# 02__Sensors_Sheet.net
KiCad netlist of a schematic drawn in Altium Designer
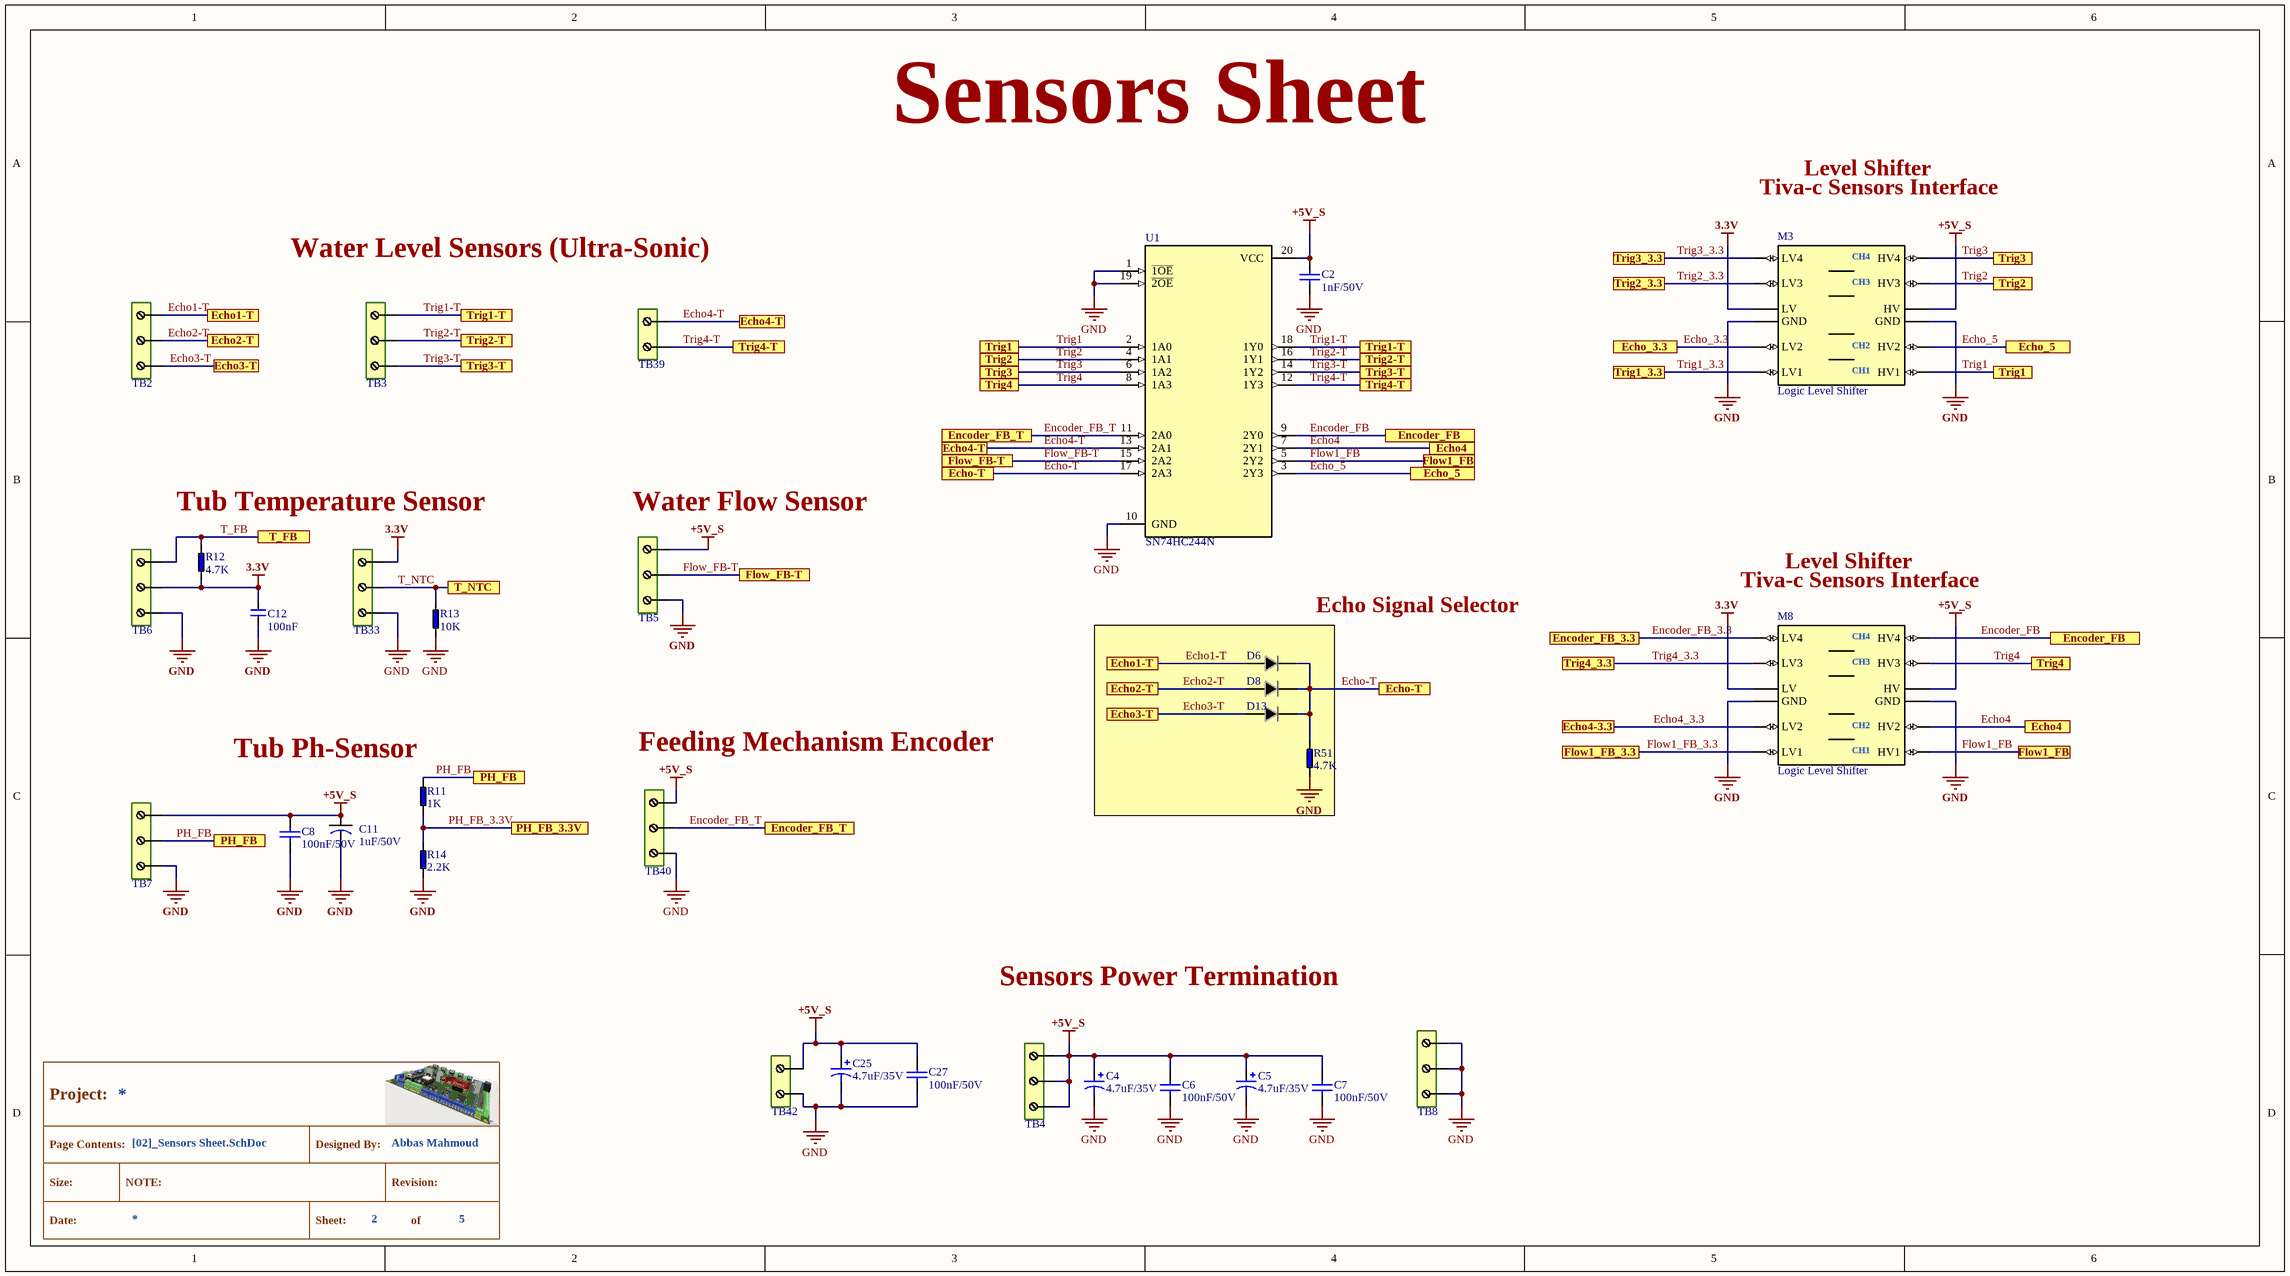
[diagram p0: [02]_Sensors Sheet.SchDoc]

(export (version "E")
  (design (tool "Eeschema 10.0.6"))
  (components
    (comp (ref "*")
      (value "Title Block")
      (description "Moatley Title Block")
      (libsource (lib "Altium_Abbas") (part "Title Block"))
    )
    (comp (ref "C2")
      (value "1nF/50V")
      (footprint "CCAP - PACKAGE - THT ,P = 2.54 MM")
      (description "1nF ±20% 50V Through Hole,P=2.54mm Ceramic Disc Capacitors RoHS")
      (libsource (lib "Altium_Abbas_V3") (part "CCAP - 1nF - 50V - THT - P = 2.54"))
    )
    (comp (ref "C4")
      (value "4.7uF/35V")
      (footprint "ECAP - THT - 5X11X2MM")
      (description "4.7uF ±20% 35V 5x11 7000Hrs @ 105℃ Radial,5x11mm Aluminum Electrolytic Capacitors - Leaded RoHS")
      (libsource (lib "Altium_Abbas_V3") (part "ECAP - 4.7uF - 35V"))
    )
    (comp (ref "C5")
      (value "4.7uF/35V")
      (footprint "ECAP - THT - 5X11X2MM")
      (description "4.7uF ±20% 35V 5x11 7000Hrs @ 105℃ Radial,5x11mm Aluminum Electrolytic Capacitors - Leaded RoHS")
      (libsource (lib "Altium_Abbas_V3") (part "ECAP - 4.7uF - 35V"))
    )
    (comp (ref "C6")
      (value "100nF/50V")
      (footprint "CCAP - PACKAGE - THT ,P = 2.54 MM")
      (description "100nF -20%~+80% 50V Through Hole,P=2.54mm Ceramic Disc Capacitors RoHS")
      (libsource (lib "Altium_Abbas_V3") (part "CCAP - 100nF - 50V - THT - P = 2.54"))
    )
    (comp (ref "C7")
      (value "100nF/50V")
      (footprint "CCAP - PACKAGE - THT ,P = 2.54 MM")
      (description "100nF -20%~+80% 50V Through Hole,P=2.54mm Ceramic Disc Capacitors RoHS")
      (libsource (lib "Altium_Abbas_V3") (part "CCAP - 100nF - 50V - THT - P = 2.54"))
    )
    (comp (ref "C8")
      (value "100nF/50V")
      (footprint "CCAP - PACKAGE - THT ,P = 2.54 MM")
      (description "100nF -20%~+80% 50V Through Hole,P=2.54mm Ceramic Disc Capacitors RoHS")
      (libsource (lib "Altium_Abbas_V3") (part "CCAP - 100nF - 50V - THT - P = 2.54"))
    )
    (comp (ref "C11")
      (value "1uF/50V")
      (footprint "ECAP 5X11X2MM")
      (description "1uF ±20% 50V 5x11 1000Hrs @ 105℃ Radial,5x11mm Aluminum Electrolytic Capacitors - Leaded RoHS")
      (libsource (lib "Altium_Abbas") (part "ECAP-1uF-50V"))
    )
    (comp (ref "C12")
      (value "100nF")
      (footprint "CCAP 0.1 N Y")
      (libsource (lib "Altium_Abbas") (part "Ceramic_CAP_100nF"))
    )
    (comp (ref "C25")
      (value "4.7uF/35V")
      (footprint "ECAP - THT - 5X11X2MM")
      (description "4.7uF ±20% 35V 5x11 7000Hrs @ 105℃ Radial,5x11mm Aluminum Electrolytic Capacitors - Leaded RoHS")
      (libsource (lib "Altium_Abbas_V3") (part "ECAP - 4.7uF - 35V"))
    )
    (comp (ref "C27")
      (value "100nF/50V")
      (footprint "CCAP - PACKAGE - THT ,P = 2.54 MM")
      (description "100nF -20%~+80% 50V Through Hole,P=2.54mm Ceramic Disc Capacitors RoHS")
      (libsource (lib "Altium_Abbas_V3") (part "CCAP - 100nF - 50V - THT - P = 2.54"))
    )
    (comp (ref "D6")
      (value "1N4007")
      (footprint "DIODE - THT - 2.54P - PACKAGE - DO-41")
      (description "1kV 1A 1V @ 1A DO-41 Diodes - General Purpose RoHS")
      (libsource (lib "Altium_Abbas_V3") (part "Diode - 1N4007 - THT"))
    )
    (comp (ref "D8")
      (value "1N4007")
      (footprint "DIODE - THT - 2.54P - PACKAGE - DO-41")
      (description "1kV 1A 1V @ 1A DO-41 Diodes - General Purpose RoHS")
      (libsource (lib "Altium_Abbas_V3") (part "Diode - 1N4007 - THT"))
    )
    (comp (ref "D13")
      (value "1N4007")
      (footprint "DIODE - THT - 2.54P - PACKAGE - DO-41")
      (description "1kV 1A 1V @ 1A DO-41 Diodes - General Purpose RoHS")
      (libsource (lib "Altium_Abbas_V3") (part "Diode - 1N4007 - THT"))
    )
    (comp (ref "M3")
      (value "Logic Level Shifter")
      (footprint "Logic Level Shifter")
      (description "Logic Level Converter Bi-Directional - Works with 5V / 3.3V / 2.8V / 1.8V")
      (libsource (lib "Altium_Modules") (part "Logic Level Shifter"))
    )
    (comp (ref "M8")
      (value "Logic Level Shifter")
      (footprint "Logic Level Shifter")
      (description "Logic Level Converter Bi-Directional - Works with 5V / 3.3V / 2.8V / 1.8V")
      (libsource (lib "Altium_Modules") (part "Logic Level Shifter"))
    )
    (comp (ref "R11")
      (value "1K")
      (footprint "R-THT_5.08mm-1/4W")
      (description "1K ±1% 1/4W ±100ppm/℃ Axial Metal Film Resistor_ Throuh Hole Technology RoHS")
      (libsource (lib "Altium_Abbas") (part "R1K-THT"))
    )
    (comp (ref "R12")
      (value "4.7K")
      (footprint "R-THT_5.08mm-1/4W")
      (description "4.7K ±1% 1/4W ±100ppm/℃ Axial Metal Film Resistor_ Throuh Hole Technology RoHS")
      (libsource (lib "Altium_Abbas") (part "R4.7K-THT"))
    )
    (comp (ref "R13")
      (value "10K")
      (footprint "R - THT - P5.0 - 1/4W")
      (description "10K ±1% 1/4W ±100ppm/℃ Axial Metal Film Resistor_ Throuh Hole Technology RoHS")
      (libsource (lib "Altium_Abbas_V3") (part "R10K - THT"))
    )
    (comp (ref "R14")
      (value "2.2K")
      (footprint "R-THT_5.08mm-1/4W")
      (description "2.2K ±1% 1/4W ±100ppm/℃ Axial Metal Film Resistor_ Throuh Hole Technology RoHS")
      (libsource (lib "Altium_Abbas") (part "R2.2K-THT"))
    )
    (comp (ref "R51")
      (value "4.7K")
      (footprint "R-THT_5.08mm-1/4W")
      (description "4.7K ±1% 1/4W ±100ppm/℃ Axial Metal Film Resistor_ Throuh Hole Technology RoHS")
      (libsource (lib "Altium_Abbas") (part "R4.7K-THT"))
    )
    (comp (ref "TB2")
      (value "3 Pins Pluggable")
      (footprint "TERMINAL BLOCK - 3 PINS - PACKAGE - PLUGGABLE - THT - P = 5.08MM - Vertical _ PLUG+RECEPTABLE")
      (libsource (lib "Altium_Abbas_V3") (part "Terminal Block - 3 Pins - Pluggable - Vertical"))
    )
    (comp (ref "TB3")
      (value "3 Pins Pluggable")
      (footprint "TERMINAL BLOCK - 3 PINS - PACKAGE - PLUGGABLE - THT - P = 5.08MM - HORIZONTAL _ PLUG+RECEPTABLE")
      (libsource (lib "Altium_Abbas_V3") (part "Terminal Block - 3 Pins - Pluggable"))
    )
    (comp (ref "TB4")
      (value "3 Pins Pluggable")
      (footprint "TERMINAL BLOCK - 3 PINS - PACKAGE - PLUGGABLE - THT - P = 5.08MM - Vertical _ PLUG+RECEPTABLE")
      (libsource (lib "Altium_Abbas_V3") (part "Terminal Block - 3 Pins - Pluggable - Vertical"))
    )
    (comp (ref "TB5")
      (value "3 Pins Pluggable")
      (footprint "TERMINAL BLOCK - 3 PINS - PACKAGE - PLUGGABLE - THT - P = 5.08MM - HORIZONTAL _ PLUG+RECEPTABLE")
      (libsource (lib "Altium_Abbas_V3") (part "Terminal Block - 3 Pins - Pluggable"))
    )
    (comp (ref "TB6")
      (value "3 Pins Pluggable")
      (footprint "TERMINAL BLOCK - 3 PINS - PACKAGE - PLUGGABLE - THT - P = 5.08MM - Vertical _ PLUG+RECEPTABLE")
      (libsource (lib "Altium_Abbas_V3") (part "Terminal Block - 3 Pins - Pluggable - Vertical"))
    )
    (comp (ref "TB7")
      (value "3 Pins Pluggable")
      (footprint "TERMINAL BLOCK - 3 PINS - PACKAGE - PLUGGABLE - THT - P = 5.08MM - Vertical _ PLUG+RECEPTABLE")
      (libsource (lib "Altium_Abbas_V3") (part "Terminal Block - 3 Pins - Pluggable - Vertical"))
    )
    (comp (ref "TB8")
      (value "3 Pins Pluggable")
      (footprint "TERMINAL BLOCK - 3 PINS - PACKAGE - PLUGGABLE - THT - P = 5.08MM - HORIZONTAL _ PLUG+RECEPTABLE")
      (libsource (lib "Altium_Abbas_V3") (part "Terminal Block - 3 Pins - Pluggable"))
    )
    (comp (ref "TB33")
      (value "3 Pins Pluggable")
      (footprint "TERMINAL BLOCK - 3 PINS - PACKAGE - PLUGGABLE - THT - P = 5.08MM - HORIZONTAL _ PLUG+RECEPTABLE")
      (libsource (lib "Altium_Abbas_V3") (part "Terminal Block - 3 Pins - Pluggable"))
    )
    (comp (ref "TB39")
      (value "2 Pins Pluggable")
      (footprint "TERMINAL BLOCK - 2 PINS - PACKAGE - PLUGGABLE - THT - P = 5.08MM - Horizontal _ Plug+Receptable")
      (libsource (lib "Altium_Abbas_V3") (part "Terminal Block - 2 Pins - Pluggable"))
    )
    (comp (ref "TB40")
      (value "3 Pins Pluggable")
      (footprint "TERMINAL BLOCK - 3 PINS - PACKAGE - PLUGGABLE - THT - P = 5.08MM - Vertical _ PLUG+RECEPTABLE")
      (libsource (lib "Altium_Abbas_V3") (part "Terminal Block - 3 Pins - Pluggable - Vertical"))
    )
    (comp (ref "TB42")
      (value "2 Pins Pluggable")
      (footprint "TERMINAL BLOCK - 2 PINS - PACKAGE - PLUGGABLE - THT - P = 5.08MM - Horizontal _ Plug+Receptable")
      (libsource (lib "Altium_Abbas_V3") (part "Terminal Block - 2 Pins - Pluggable"))
    )
    (comp (ref "U1")
      (value "SN74HC244N")
      (footprint "ICB - DIP-20")
      (description "74HC Buffers,Non-Opposite Side DIP-20 Logic-Buffers, Drivers, Receivers, Transceivers RoHS")
      (libsource (lib "Altium_Abbas_V3") (part "IC - SN74HC244N"))
    )
  )
  (nets
    (net (code "1") (name "+5V_S") (class "Default")
      (node (ref "C11") (pin "A") (pintype "passive"))
      (node (ref "C2") (pin "1") (pinfunction "1_1") (pintype "passive"))
      (node (ref "C25") (pin "A") (pinfunction "A_A") (pintype "passive"))
      (node (ref "C27") (pin "1") (pinfunction "1_1") (pintype "passive"))
      (node (ref "C4") (pin "A") (pinfunction "A_A") (pintype "passive"))
      (node (ref "C5") (pin "A") (pinfunction "A_A") (pintype "passive"))
      (node (ref "C6") (pin "1") (pinfunction "1_1") (pintype "passive"))
      (node (ref "C7") (pin "1") (pinfunction "1_1") (pintype "passive"))
      (node (ref "C8") (pin "1") (pinfunction "1_1") (pintype "passive"))
      (node (ref "M3") (pin "4") (pinfunction "HV_4") (pintype "passive"))
      (node (ref "M8") (pin "4") (pinfunction "HV_4") (pintype "passive"))
      (node (ref "TB4") (pin "1") (pinfunction "1_1") (pintype "passive"))
      (node (ref "TB4") (pin "2") (pinfunction "2_2") (pintype "passive"))
      (node (ref "TB4") (pin "3") (pinfunction "3_3") (pintype "passive"))
      (node (ref "TB40") (pin "3") (pinfunction "3_3") (pintype "passive"))
      (node (ref "TB42") (pin "2") (pinfunction "2_2") (pintype "passive"))
      (node (ref "TB5") (pin "3") (pinfunction "3_3") (pintype "passive"))
      (node (ref "TB7") (pin "3") (pinfunction "3_3") (pintype "passive"))
      (node (ref "U1") (pin "20") (pinfunction "VCC_20") (pintype "power_in"))
    )
    (net (code "2") (name "/Echo-T") (class "Default")
      (node (ref "D13") (pin "K") (pinfunction "K_K") (pintype "passive"))
      (node (ref "D6") (pin "K") (pinfunction "K_K") (pintype "passive"))
      (node (ref "D8") (pin "K") (pinfunction "K_K") (pintype "passive"))
      (node (ref "R51") (pin "2") (pinfunction "6_2") (pintype "passive"))
      (node (ref "U1") (pin "17") (pinfunction "2A3_17") (pintype "input"))
    )
    (net (code "3") (name "/Echo1-T") (class "Default")
      (node (ref "D6") (pin "A") (pinfunction "A_A") (pintype "passive"))
      (node (ref "TB2") (pin "3") (pinfunction "3_3") (pintype "passive"))
    )
    (net (code "4") (name "/Echo2-T") (class "Default")
      (node (ref "D8") (pin "A") (pinfunction "A_A") (pintype "passive"))
      (node (ref "TB2") (pin "2") (pinfunction "2_2") (pintype "passive"))
    )
    (net (code "5") (name "/Echo3-T") (class "Default")
      (node (ref "D13") (pin "A") (pinfunction "A_A") (pintype "passive"))
      (node (ref "TB2") (pin "1") (pinfunction "1_1") (pintype "passive"))
    )
    (net (code "6") (name "/Echo4") (class "Default")
      (node (ref "M8") (pin "5") (pinfunction "HV2_5") (pintype "bidirectional"))
      (node (ref "U1") (pin "7") (pinfunction "2Y1_7") (pintype "output"))
    )
    (net (code "7") (name "/Echo4-T") (class "Default")
      (node (ref "TB39") (pin "2") (pinfunction "2_2") (pintype "passive"))
      (node (ref "U1") (pin "13") (pinfunction "2A1_13") (pintype "input"))
    )
    (net (code "8") (name "/Echo4_3.3") (class "Default")
      (node (ref "M8") (pin "8") (pinfunction "LV2_8") (pintype "bidirectional"))
    )
    (net (code "9") (name "/Echo_3.3") (class "Default")
      (node (ref "M3") (pin "8") (pinfunction "LV2_8") (pintype "bidirectional"))
    )
    (net (code "10") (name "/Echo_5") (class "Default")
      (node (ref "M3") (pin "5") (pinfunction "HV2_5") (pintype "bidirectional"))
      (node (ref "U1") (pin "3") (pinfunction "2Y3_3") (pintype "output"))
    )
    (net (code "11") (name "/Encoder_FB") (class "Default")
      (node (ref "M8") (pin "1") (pinfunction "HV4_1") (pintype "bidirectional"))
      (node (ref "U1") (pin "9") (pinfunction "2Y0_9") (pintype "output"))
    )
    (net (code "12") (name "/Encoder_FB_3.3") (class "Default")
      (node (ref "M8") (pin "12") (pinfunction "LV4_12") (pintype "bidirectional"))
    )
    (net (code "13") (name "/Encoder_FB_T") (class "Default")
      (node (ref "TB40") (pin "2") (pinfunction "2_2") (pintype "passive"))
      (node (ref "U1") (pin "11") (pinfunction "2A0_11") (pintype "input"))
    )
    (net (code "14") (name "/Flow1_FB") (class "Default")
      (node (ref "M8") (pin "6") (pinfunction "HV1_6") (pintype "bidirectional"))
      (node (ref "U1") (pin "5") (pinfunction "2Y2_5") (pintype "output"))
    )
    (net (code "15") (name "/Flow1_FB_3.3") (class "Default")
      (node (ref "M8") (pin "7") (pinfunction "LV1_7") (pintype "bidirectional"))
    )
    (net (code "16") (name "/Flow_FB-T") (class "Default")
      (node (ref "TB5") (pin "2") (pinfunction "2_2") (pintype "passive"))
      (node (ref "U1") (pin "15") (pinfunction "2A2_15") (pintype "input"))
    )
    (net (code "17") (name "/PH_FB") (class "Default")
      (node (ref "R11") (pin "2") (pinfunction "6_2") (pintype "passive"))
      (node (ref "TB7") (pin "2") (pinfunction "2_2") (pintype "passive"))
    )
    (net (code "18") (name "/PH_FB_3.3V") (class "Default")
      (node (ref "R11") (pin "1") (pinfunction "5_1") (pintype "passive"))
      (node (ref "R14") (pin "2") (pinfunction "6_2") (pintype "passive"))
    )
    (net (code "19") (name "/T_FB") (class "Default")
      (node (ref "R12") (pin "1") (pinfunction "5_1") (pintype "passive"))
      (node (ref "TB6") (pin "3") (pinfunction "3_3") (pintype "passive"))
    )
    (net (code "20") (name "/T_NTC") (class "Default")
      (node (ref "R13") (pin "2") (pinfunction "6_2") (pintype "passive"))
      (node (ref "TB33") (pin "2") (pinfunction "2_2") (pintype "passive"))
    )
    (net (code "21") (name "/Trig1") (class "Default")
      (node (ref "M3") (pin "6") (pinfunction "HV1_6") (pintype "bidirectional"))
      (node (ref "U1") (pin "2") (pinfunction "1A0_2") (pintype "input"))
    )
    (net (code "22") (name "/Trig1-T") (class "Default")
      (node (ref "TB3") (pin "3") (pinfunction "3_3") (pintype "passive"))
      (node (ref "U1") (pin "18") (pinfunction "1Y0_18") (pintype "output"))
    )
    (net (code "23") (name "/Trig1_3.3") (class "Default")
      (node (ref "M3") (pin "7") (pinfunction "LV1_7") (pintype "bidirectional"))
    )
    (net (code "24") (name "/Trig2") (class "Default")
      (node (ref "M3") (pin "2") (pinfunction "HV3_2") (pintype "bidirectional"))
      (node (ref "U1") (pin "4") (pinfunction "1A1_4") (pintype "input"))
    )
    (net (code "25") (name "/Trig2-T") (class "Default")
      (node (ref "TB3") (pin "2") (pinfunction "2_2") (pintype "passive"))
      (node (ref "U1") (pin "16") (pinfunction "1Y1_16") (pintype "output"))
    )
    (net (code "26") (name "/Trig2_3.3") (class "Default")
      (node (ref "M3") (pin "11") (pinfunction "LV3_11") (pintype "bidirectional"))
    )
    (net (code "27") (name "/Trig3") (class "Default")
      (node (ref "M3") (pin "1") (pinfunction "HV4_1") (pintype "bidirectional"))
      (node (ref "U1") (pin "6") (pinfunction "1A2_6") (pintype "input"))
    )
    (net (code "28") (name "/Trig3-T") (class "Default")
      (node (ref "TB3") (pin "1") (pinfunction "1_1") (pintype "passive"))
      (node (ref "U1") (pin "14") (pinfunction "1Y2_14") (pintype "output"))
    )
    (net (code "29") (name "/Trig3_3.3") (class "Default")
      (node (ref "M3") (pin "12") (pinfunction "LV4_12") (pintype "bidirectional"))
    )
    (net (code "30") (name "/Trig4") (class "Default")
      (node (ref "M8") (pin "2") (pinfunction "HV3_2") (pintype "bidirectional"))
      (node (ref "U1") (pin "8") (pinfunction "1A3_8") (pintype "input"))
    )
    (net (code "31") (name "/Trig4-T") (class "Default")
      (node (ref "TB39") (pin "1") (pinfunction "1_1") (pintype "passive"))
      (node (ref "U1") (pin "12") (pinfunction "1Y3_12") (pintype "output"))
    )
    (net (code "32") (name "/Trig4_3.3") (class "Default")
      (node (ref "M8") (pin "11") (pinfunction "LV3_11") (pintype "bidirectional"))
    )
    (net (code "33") (name "3.3V") (class "Default")
      (node (ref "C12") (pin "1") (pintype "passive"))
      (node (ref "M3") (pin "9") (pinfunction "LV_9") (pintype "passive"))
      (node (ref "M8") (pin "9") (pinfunction "LV_9") (pintype "passive"))
      (node (ref "R12") (pin "2") (pinfunction "6_2") (pintype "passive"))
      (node (ref "TB33") (pin "3") (pinfunction "3_3") (pintype "passive"))
      (node (ref "TB6") (pin "2") (pinfunction "2_2") (pintype "passive"))
    )
    (net (code "34") (name "GND") (class "Default")
      (node (ref "C11") (pin "K") (pintype "passive"))
      (node (ref "C12") (pin "2") (pintype "passive"))
      (node (ref "C2") (pin "2") (pinfunction "2_2") (pintype "passive"))
      (node (ref "C25") (pin "K") (pinfunction "K_K") (pintype "passive"))
      (node (ref "C27") (pin "2") (pinfunction "2_2") (pintype "passive"))
      (node (ref "C4") (pin "K") (pinfunction "K_K") (pintype "passive"))
      (node (ref "C5") (pin "K") (pinfunction "K_K") (pintype "passive"))
      (node (ref "C6") (pin "2") (pinfunction "2_2") (pintype "passive"))
      (node (ref "C7") (pin "2") (pinfunction "2_2") (pintype "passive"))
      (node (ref "C8") (pin "2") (pinfunction "2_2") (pintype "passive"))
      (node (ref "M3") (pin "10") (pinfunction "GND_10") (pintype "passive"))
      (node (ref "M3") (pin "3") (pinfunction "GND_3") (pintype "passive"))
      (node (ref "M8") (pin "10") (pinfunction "GND_10") (pintype "passive"))
      (node (ref "M8") (pin "3") (pinfunction "GND_3") (pintype "passive"))
      (node (ref "R13") (pin "1") (pinfunction "5_1") (pintype "passive"))
      (node (ref "R14") (pin "1") (pinfunction "5_1") (pintype "passive"))
      (node (ref "R51") (pin "1") (pinfunction "5_1") (pintype "passive"))
      (node (ref "TB33") (pin "1") (pinfunction "1_1") (pintype "passive"))
      (node (ref "TB40") (pin "1") (pinfunction "1_1") (pintype "passive"))
      (node (ref "TB42") (pin "1") (pinfunction "1_1") (pintype "passive"))
      (node (ref "TB5") (pin "1") (pinfunction "1_1") (pintype "passive"))
      (node (ref "TB6") (pin "1") (pinfunction "1_1") (pintype "passive"))
      (node (ref "TB7") (pin "1") (pinfunction "1_1") (pintype "passive"))
      (node (ref "TB8") (pin "1") (pinfunction "1_1") (pintype "passive"))
      (node (ref "TB8") (pin "2") (pinfunction "2_2") (pintype "passive"))
      (node (ref "TB8") (pin "3") (pinfunction "3_3") (pintype "passive"))
      (node (ref "U1") (pin "1") (pinfunction "~{1OE}_1") (pintype "input"))
      (node (ref "U1") (pin "10") (pinfunction "GND_10") (pintype "power_in"))
      (node (ref "U1") (pin "19") (pinfunction "~{2OE}_19") (pintype "input"))
    )
  )
)
